# Adafruit_AT42QT1010_Breakout.net
KiCad netlist of a schematic drawn in EAGLE
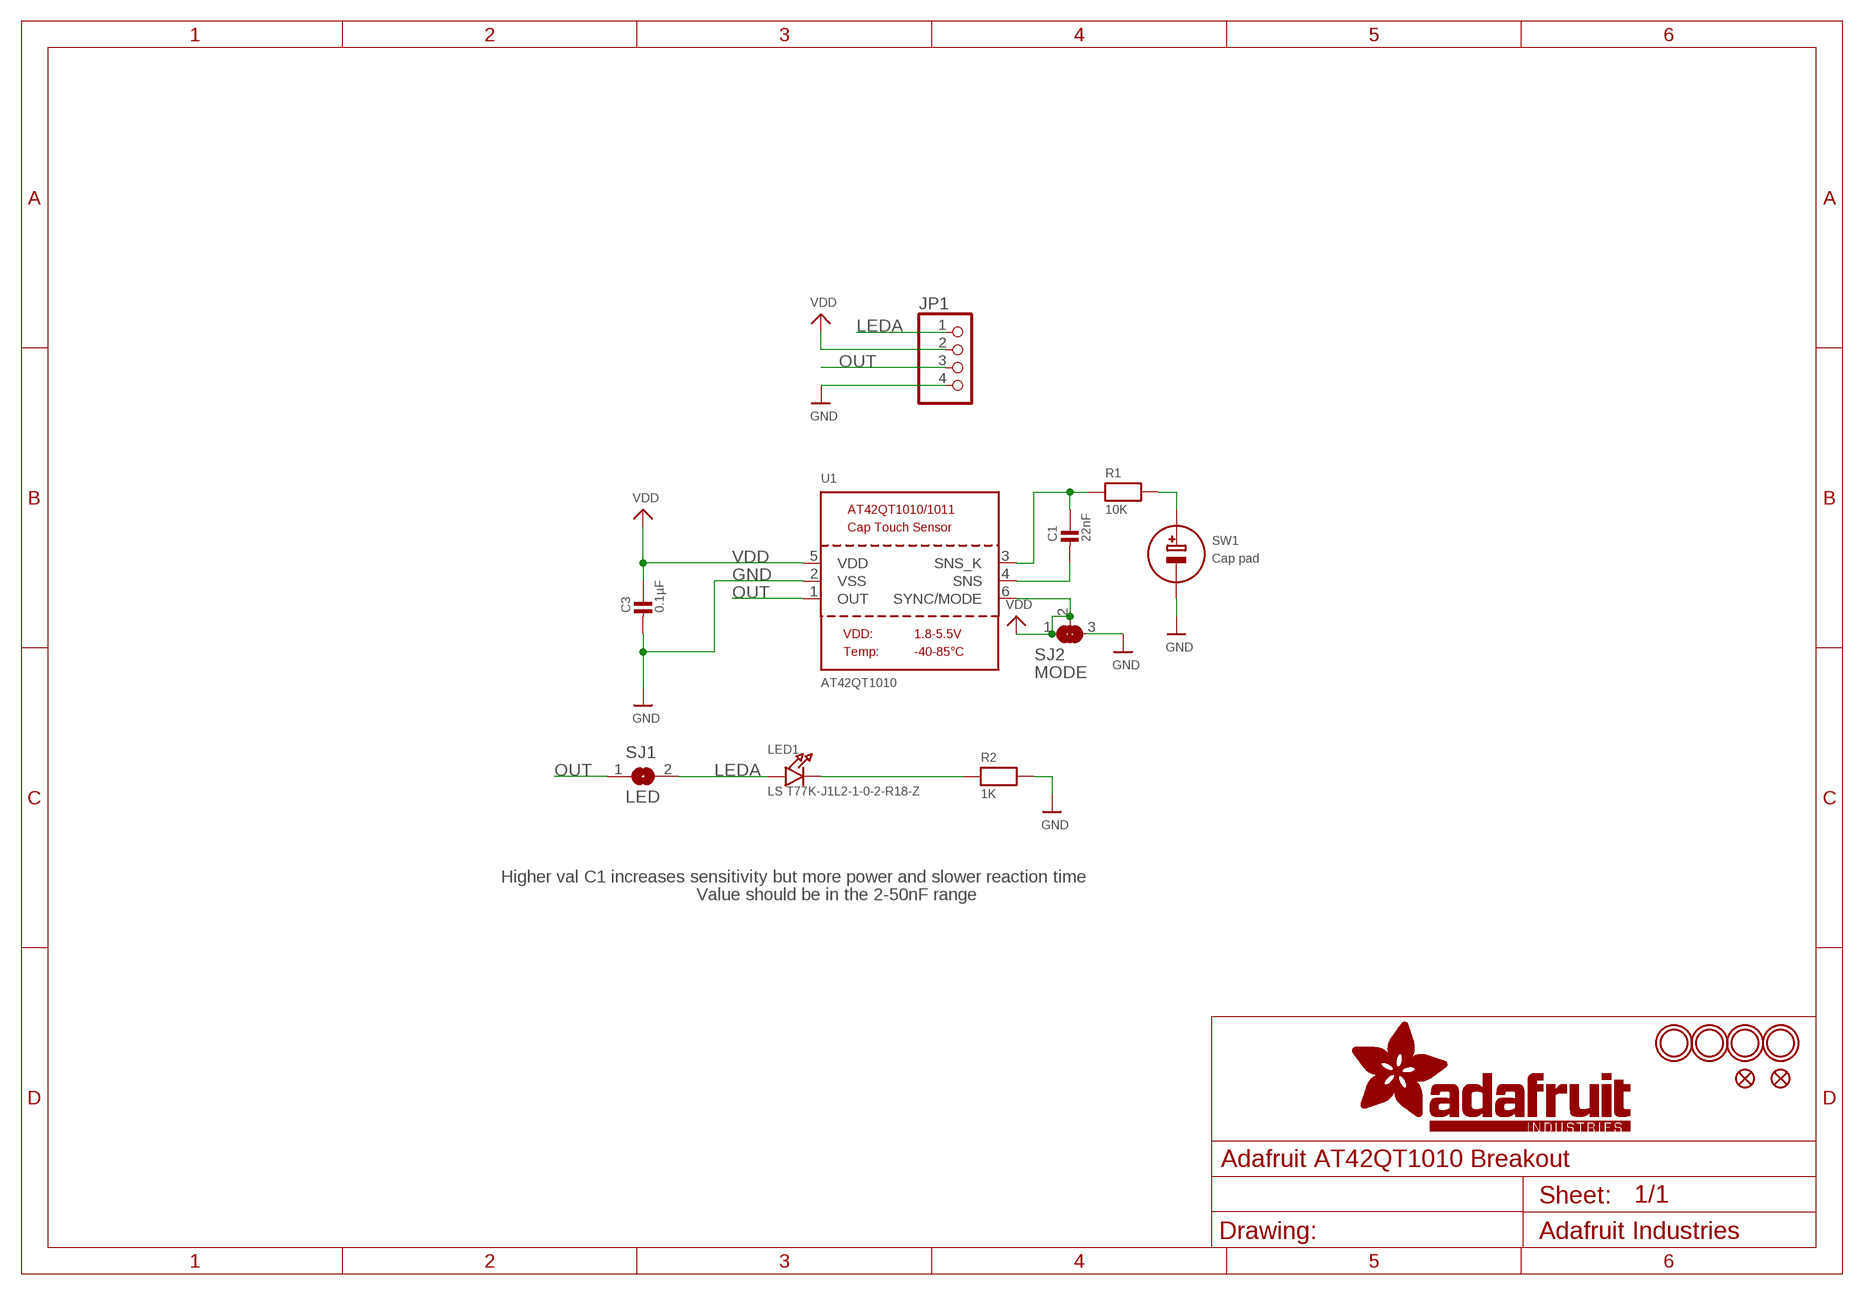
[diagram p0: schematic, sheet 1]

(export (version "E")
  (design (tool "Eeschema 10.0.6"))
  (components
    (comp (ref "C1")
      (value "22nF")
      (footprint "eagle-import:_0805")
      (libsource (lib "eagle-import") (part "CAP_CERAMIC_0805"))
    )
    (comp (ref "C3")
      (value "0.1µF")
      (footprint "eagle-import:_0805")
      (libsource (lib "eagle-import") (part "CAP_CERAMIC_0805"))
    )
    (comp (ref "FID1")
      (value "FIDUCIAL\"\"")
      (footprint "eagle-import:FIDUCIAL_1MM")
      (libsource (lib "eagle-import") (part "FIDUCIAL{dblquote}{dblquote}"))
    )
    (comp (ref "FID2")
      (value "FIDUCIAL\"\"")
      (footprint "eagle-import:FIDUCIAL_1MM")
      (libsource (lib "eagle-import") (part "FIDUCIAL{dblquote}{dblquote}"))
    )
    (comp (ref "JP1")
      (value "HEADER-1X476MIL")
      (footprint "eagle-import:1X04_ROUND_76")
      (libsource (lib "eagle-import") (part "HEADER-1X476MIL"))
    )
    (comp (ref "LED1")
      (value "LS T77K-J1L2-1-0-2-R18-Z")
      (footprint "eagle-import:PLCC2_REVMOUNT")
      (libsource (lib "eagle-import") (part "LEDPLCC2_REV"))
    )
    (comp (ref "R1")
      (value "10K")
      (footprint "eagle-import:_0805")
      (libsource (lib "eagle-import") (part "RESISTOR_0805"))
    )
    (comp (ref "R2")
      (value "1K")
      (footprint "eagle-import:_0805")
      (libsource (lib "eagle-import") (part "RESISTOR_0805"))
    )
    (comp (ref "SJ1")
      (value "LED")
      (footprint "eagle-import:SOLDERJUMPER_CLOSEDWIRE")
      (libsource (lib "eagle-import") (part "SOLDERJUMPERCLOSED"))
    )
    (comp (ref "SJ2")
      (value "MODE")
      (footprint "eagle-import:SOLDERJUMPER_2WAY_OPEN_NOPASTE")
      (libsource (lib "eagle-import") (part "SOLDERJUMPER_2WAY"))
    )
    (comp (ref "SW1")
      (value "Cap pad")
      (footprint "eagle-import:CAPTOUCH_SIMPLE_12.5MM")
      (libsource (lib "eagle-import") (part "SWITCH_CAPTOUCHATMELAT42QT"))
    )
    (comp (ref "U$6")
      (value "MOUNTINGHOLE2.5")
      (footprint "eagle-import:MOUNTINGHOLE_2.5_PLATED")
      (libsource (lib "eagle-import") (part "MOUNTINGHOLE2.5"))
    )
    (comp (ref "U$9")
      (value "MOUNTINGHOLE2.5")
      (footprint "eagle-import:MOUNTINGHOLE_2.5_PLATED")
      (libsource (lib "eagle-import") (part "MOUNTINGHOLE2.5"))
    )
    (comp (ref "U$10")
      (value "MOUNTINGHOLE2.5")
      (footprint "eagle-import:MOUNTINGHOLE_2.5_PLATED")
      (libsource (lib "eagle-import") (part "MOUNTINGHOLE2.5"))
    )
    (comp (ref "U$11")
      (value "MOUNTINGHOLE2.5")
      (footprint "eagle-import:MOUNTINGHOLE_2.5_PLATED")
      (libsource (lib "eagle-import") (part "MOUNTINGHOLE2.5"))
    )
    (comp (ref "U1")
      (value "AT42QT1010")
      (footprint "eagle-import:SOT23-6")
      (libsource (lib "eagle-import") (part "AT42QT1010/1"))
    )
  )
  (nets
    (net (code "1") (name "/LEDA") (class "Default")
      (node (ref "JP1") (pin "1") (pinfunction "1_1") (pintype "passive"))
      (node (ref "LED1") (pin "A") (pinfunction "A_A") (pintype "passive"))
      (node (ref "SJ1") (pin "2") (pinfunction "2_2") (pintype "passive"))
    )
    (net (code "2") (name "/OUT") (class "Default")
      (node (ref "JP1") (pin "3") (pinfunction "3_3") (pintype "passive"))
      (node (ref "SJ1") (pin "1") (pinfunction "1_1") (pintype "passive"))
      (node (ref "U1") (pin "1") (pinfunction "OUT_1") (pintype "output"))
    )
    (net (code "3") (name "GND") (class "Default")
      (node (ref "C3") (pin "2") (pinfunction "P$2_2") (pintype "passive"))
      (node (ref "JP1") (pin "4") (pinfunction "4_4") (pintype "passive"))
      (node (ref "R2") (pin "2") (pinfunction "2_2") (pintype "passive"))
      (node (ref "SJ2") (pin "3") (pinfunction "3_3") (pintype "passive"))
      (node (ref "SW1") (pin "G") (pinfunction "-_G") (pintype "passive"))
      (node (ref "U1") (pin "2") (pinfunction "VSS_2") (pintype "power_in"))
    )
    (net (code "4") (name "Net-(C1-P$1)") (class "Default")
      (node (ref "C1") (pin "1") (pinfunction "P$1_1") (pintype "passive"))
      (node (ref "R1") (pin "1") (pinfunction "1_1") (pintype "passive"))
      (node (ref "U1") (pin "3") (pinfunction "SNS_K_3") (pintype "bidirectional"))
    )
    (net (code "5") (name "Net-(C1-P$2)") (class "Default")
      (node (ref "C1") (pin "2") (pinfunction "P$2_2") (pintype "passive"))
      (node (ref "U1") (pin "4") (pinfunction "SNS_4") (pintype "bidirectional"))
    )
    (net (code "6") (name "Net-(LED1-C)") (class "Default")
      (node (ref "LED1") (pin "K") (pinfunction "C_K") (pintype "passive"))
      (node (ref "R2") (pin "1") (pinfunction "1_1") (pintype "passive"))
    )
    (net (code "7") (name "Net-(SW1-+)") (class "Default")
      (node (ref "R1") (pin "2") (pinfunction "2_2") (pintype "passive"))
      (node (ref "SW1") (pin "E") (pinfunction "+_E") (pintype "passive"))
    )
    (net (code "8") (name "VDD") (class "Default")
      (node (ref "C3") (pin "1") (pinfunction "P$1_1") (pintype "passive"))
      (node (ref "JP1") (pin "2") (pinfunction "2_2") (pintype "passive"))
      (node (ref "SJ2") (pin "1") (pinfunction "1_1") (pintype "passive"))
      (node (ref "SJ2") (pin "2") (pinfunction "2_2") (pintype "passive"))
      (node (ref "U1") (pin "5") (pinfunction "VDD_5") (pintype "power_in"))
      (node (ref "U1") (pin "6") (pinfunction "SYNC/MODE_6") (pintype "input"))
    )
  )
)
